# ADS-228.net
KiCad netlist of a schematic drawn in Altium Designer
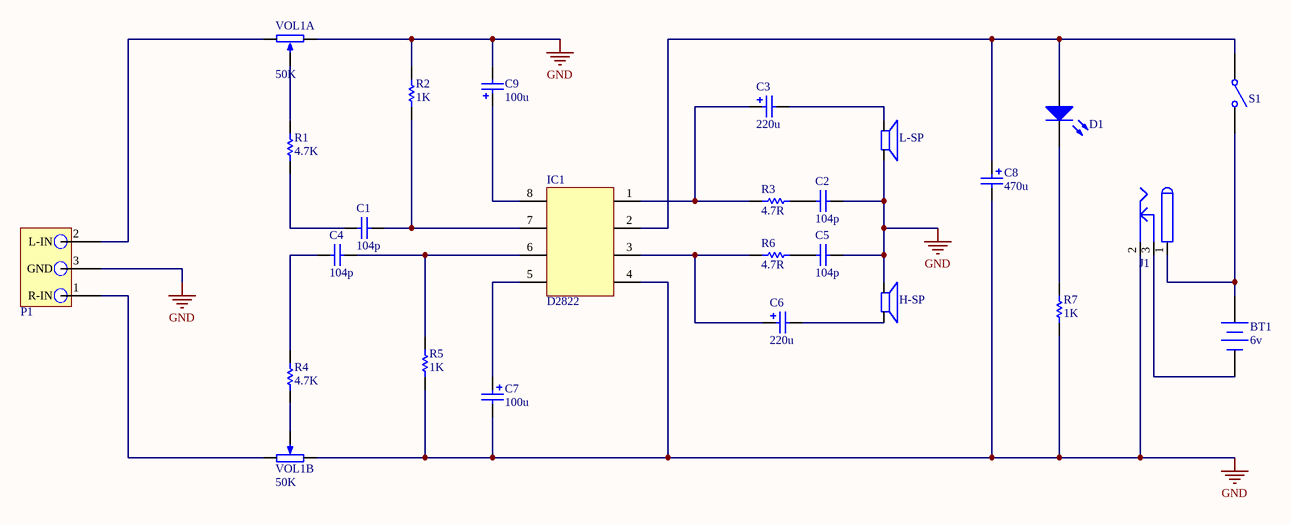
[diagram p0: ADS-228.SchDoc]

(export (version "E")
  (design (tool "Eeschema 10.0.6"))
  (components
    (comp (ref "BT1")
      (value "6v")
      (footprint "BAT")
      (description "Multicell Battery")
      (fields (field (name "PUBLISHER") "Altium Limited"))
      (libsource (lib "ADS-228") (part "Battery"))
    )
    (comp (ref "C1")
      (value "104p")
      (footprint "RAD3")
      (description "Capacitor")
      (fields (field (name "Comment") "Cap") (field (name "PUBLISHER") "Altium Limited"))
      (libsource (lib "ADS-228") (part "Cap"))
    )
    (comp (ref "C2")
      (value "104p")
      (footprint "RAD3")
      (description "Capacitor")
      (fields (field (name "Comment") "Cap") (field (name "PUBLISHER") "Altium Limited"))
      (libsource (lib "ADS-228") (part "Cap"))
    )
    (comp (ref "C3")
      (value "220u")
      (footprint "CAPPR3-5")
      (description "Polarized Capacitor (Radial)")
      (fields (field (name "Comment") "Cap Pol1") (field (name "PUBLISHER") "Altium Limited"))
      (libsource (lib "ADS-228") (part "Cap Pol1"))
    )
    (comp (ref "C4")
      (value "104p")
      (footprint "RAD3")
      (description "Capacitor")
      (fields (field (name "Comment") "Cap") (field (name "PUBLISHER") "Altium Limited"))
      (libsource (lib "ADS-228") (part "Cap"))
    )
    (comp (ref "C5")
      (value "104p")
      (footprint "RAD3")
      (description "Capacitor")
      (fields (field (name "Comment") "Cap") (field (name "PUBLISHER") "Altium Limited"))
      (libsource (lib "ADS-228") (part "Cap"))
    )
    (comp (ref "C6")
      (value "220u")
      (footprint "CAPPR3-5")
      (description "Polarized Capacitor (Radial)")
      (fields (field (name "Comment") "Cap Pol1") (field (name "PUBLISHER") "Altium Limited"))
      (libsource (lib "ADS-228") (part "Cap Pol1"))
    )
    (comp (ref "C7")
      (value "100u")
      (footprint "CAPPR4-6")
      (description "Polarized Capacitor (Radial)")
      (fields (field (name "Comment") "Cap Pol1") (field (name "PUBLISHER") "Altium Limited"))
      (libsource (lib "ADS-228") (part "Cap Pol1"))
    )
    (comp (ref "C8")
      (value "470u")
      (footprint "CAPPR4-6")
      (description "Polarized Capacitor (Radial)")
      (fields (field (name "Comment") "Cap Pol1") (field (name "PUBLISHER") "Altium Limited"))
      (libsource (lib "ADS-228") (part "Cap Pol1"))
    )
    (comp (ref "C9")
      (value "100u")
      (footprint "CAPPR3-5")
      (description "Polarized Capacitor (Radial)")
      (fields (field (name "Comment") "Cap Pol1") (field (name "PUBLISHER") "Altium Limited"))
      (libsource (lib "ADS-228") (part "Cap Pol1"))
    )
    (comp (ref "D1")
      (value "LED1")
      (footprint "LED")
      (description "Typical RED GaAs LED")
      (fields (field (name "PUBLISHER") "Altium Limited"))
      (libsource (lib "ADS-228") (part "LED1"))
    )
    (comp (ref "H-SP") (value "SPEAKER") (footprint "SPAKER2") (libsource (lib "ADS-228") (part "SPEAKER")))
    (comp (ref "IC1") (value "D2822") (footprint "DIP8") (libsource (lib "ADS-228") (part "D2822")))
    (comp (ref "J1")
      (value "PWR2.5")
      (footprint "DC")
      (description "Low Voltage Power Supply Connector")
      (fields (field (name "PUBLISHER") "Altium Limited"))
      (libsource (lib "ADS-228") (part "PWR2.5"))
    )
    (comp (ref "L-SP") (value "SPEAKER") (footprint "SPAKER2") (libsource (lib "ADS-228") (part "SPEAKER")))
    (comp (ref "P1") (value "PLUG") (footprint "HDR1X3") (libsource (lib "ADS-228") (part "PLUG")))
    (comp (ref "R1")
      (value "4.7K")
      (footprint "AXIAL3")
      (description "Resistor")
      (fields (field (name "Comment") "Res1") (field (name "PUBLISHER") "Altium Limited"))
      (libsource (lib "ADS-228") (part "Res1"))
    )
    (comp (ref "R2")
      (value "1K")
      (footprint "AXIAL3")
      (description "Resistor")
      (fields (field (name "Comment") "Res1") (field (name "PUBLISHER") "Altium Limited"))
      (libsource (lib "ADS-228") (part "Res1"))
    )
    (comp (ref "R3")
      (value "4.7R")
      (footprint "AXIAL3")
      (description "Resistor")
      (fields (field (name "Comment") "Res1") (field (name "PUBLISHER") "Altium Limited"))
      (libsource (lib "ADS-228") (part "Res1"))
    )
    (comp (ref "R4")
      (value "4.7K")
      (footprint "AXIAL3")
      (description "Resistor")
      (fields (field (name "Comment") "Res1") (field (name "PUBLISHER") "Altium Limited"))
      (libsource (lib "ADS-228") (part "Res1"))
    )
    (comp (ref "R5")
      (value "1K")
      (footprint "AXIAL3.8")
      (description "Resistor")
      (fields (field (name "Comment") "Res1") (field (name "PUBLISHER") "Altium Limited"))
      (libsource (lib "ADS-228") (part "Res1"))
    )
    (comp (ref "R6")
      (value "4.7R")
      (footprint "AXIAL3")
      (description "Resistor")
      (fields (field (name "Comment") "Res1") (field (name "PUBLISHER") "Altium Limited"))
      (libsource (lib "ADS-228") (part "Res1"))
    )
    (comp (ref "R7")
      (value "1K")
      (footprint "AXIAL5")
      (description "Resistor")
      (fields (field (name "Comment") "Res1") (field (name "PUBLISHER") "Altium Limited"))
      (libsource (lib "ADS-228") (part "Res1"))
    )
    (comp (ref "S1")
      (value "SW-SPST")
      (footprint "SW")
      (description "Single-Pole, Single-Throw Switch")
      (fields (field (name "PUBLISHER") "Altium Limited"))
      (libsource (lib "ADS-228") (part "SW-SPST"))
    )
    (comp (ref "VOL1")
      (value "50K")
      (footprint "VR")
      (fields (field (name "Comment") "RPOT"))
      (libsource (lib "ADS-228") (part "RPOT"))
    )
  )
  (nets
    (net (code "1") (name "GND") (class "Default")
      (node (ref "C2") (pin "2") (pinfunction "2_2") (pintype "passive"))
      (node (ref "C5") (pin "2") (pinfunction "2_2") (pintype "passive"))
      (node (ref "C7") (pin "2") (pinfunction "2_2") (pintype "passive"))
      (node (ref "C8") (pin "2") (pinfunction "2_2") (pintype "passive"))
      (node (ref "C9") (pin "2") (pinfunction "2_2") (pintype "passive"))
      (node (ref "H-SP") (pin "1") (pinfunction "1_1") (pintype "passive"))
      (node (ref "IC1") (pin "4") (pinfunction "4_4") (pintype "passive"))
      (node (ref "J1") (pin "2") (pinfunction "2_2") (pintype "power_in"))
      (node (ref "L-SP") (pin "2") (pinfunction "2_2") (pintype "passive"))
      (node (ref "P1") (pin "3") (pinfunction "GND_3") (pintype "power_in"))
      (node (ref "R2") (pin "2") (pinfunction "2_2") (pintype "passive"))
      (node (ref "R5") (pin "1") (pinfunction "1_1") (pintype "passive"))
      (node (ref "R7") (pin "1") (pinfunction "1_1") (pintype "passive"))
      (node (ref "S1") (pin "0") (pinfunction "GND_0") (pintype "power_in"))
      (node (ref "VOL1") (pin "0") (pinfunction "GND_0") (pintype "power_in"))
      (node (ref "VOL1") (pin "2") (pinfunction "2_2") (pintype "passive"))
    )
    (net (code "2") (name "Net-(BT1-+)") (class "Default")
      (node (ref "BT1") (pin "1") (pinfunction "+_1") (pintype "passive"))
      (node (ref "J1") (pin "1") (pinfunction "1_1") (pintype "power_in"))
      (node (ref "S1") (pin "2") (pinfunction "2_2") (pintype "passive"))
    )
    (net (code "3") (name "Net-(BT1--)") (class "Default")
      (node (ref "BT1") (pin "2") (pinfunction "-_2") (pintype "passive"))
      (node (ref "J1") (pin "3") (pinfunction "3_3") (pintype "power_in"))
    )
    (net (code "4") (name "Net-(C1-Pad1)") (class "Default")
      (node (ref "C1") (pin "1") (pinfunction "1_1") (pintype "passive"))
      (node (ref "R1") (pin "1") (pinfunction "1_1") (pintype "passive"))
    )
    (net (code "5") (name "Net-(C1-Pad2)") (class "Default")
      (node (ref "C1") (pin "2") (pinfunction "2_2") (pintype "passive"))
      (node (ref "IC1") (pin "7") (pinfunction "7_7") (pintype "passive"))
      (node (ref "R2") (pin "1") (pinfunction "1_1") (pintype "passive"))
    )
    (net (code "6") (name "Net-(C2-Pad1)") (class "Default")
      (node (ref "C2") (pin "1") (pinfunction "1_1") (pintype "passive"))
      (node (ref "R3") (pin "2") (pinfunction "2_2") (pintype "passive"))
    )
    (net (code "7") (name "Net-(C3-Pad1)") (class "Default")
      (node (ref "C3") (pin "1") (pinfunction "1_1") (pintype "passive"))
      (node (ref "IC1") (pin "1") (pinfunction "1_1") (pintype "passive"))
      (node (ref "R3") (pin "1") (pinfunction "1_1") (pintype "passive"))
    )
    (net (code "8") (name "Net-(C3-Pad2)") (class "Default")
      (node (ref "C3") (pin "2") (pinfunction "2_2") (pintype "passive"))
      (node (ref "L-SP") (pin "1") (pinfunction "1_1") (pintype "passive"))
    )
    (net (code "9") (name "Net-(C4-Pad1)") (class "Default")
      (node (ref "C4") (pin "1") (pinfunction "1_1") (pintype "passive"))
      (node (ref "R4") (pin "2") (pinfunction "2_2") (pintype "passive"))
    )
    (net (code "10") (name "Net-(C4-Pad2)") (class "Default")
      (node (ref "C4") (pin "2") (pinfunction "2_2") (pintype "passive"))
      (node (ref "IC1") (pin "6") (pinfunction "6_6") (pintype "passive"))
      (node (ref "R5") (pin "2") (pinfunction "2_2") (pintype "passive"))
    )
    (net (code "11") (name "Net-(C5-Pad1)") (class "Default")
      (node (ref "C5") (pin "1") (pinfunction "1_1") (pintype "passive"))
      (node (ref "R6") (pin "2") (pinfunction "2_2") (pintype "passive"))
    )
    (net (code "12") (name "Net-(C6-Pad1)") (class "Default")
      (node (ref "C6") (pin "1") (pinfunction "1_1") (pintype "passive"))
      (node (ref "IC1") (pin "3") (pinfunction "3_3") (pintype "passive"))
      (node (ref "R6") (pin "1") (pinfunction "1_1") (pintype "passive"))
    )
    (net (code "13") (name "Net-(C6-Pad2)") (class "Default")
      (node (ref "C6") (pin "2") (pinfunction "2_2") (pintype "passive"))
      (node (ref "H-SP") (pin "2") (pinfunction "2_2") (pintype "passive"))
    )
    (net (code "14") (name "Net-(C7-Pad1)") (class "Default")
      (node (ref "C7") (pin "1") (pinfunction "1_1") (pintype "passive"))
      (node (ref "IC1") (pin "5") (pinfunction "5_5") (pintype "passive"))
    )
    (net (code "15") (name "Net-(C9-Pad1)") (class "Default")
      (node (ref "C9") (pin "1") (pinfunction "1_1") (pintype "passive"))
      (node (ref "IC1") (pin "8") (pinfunction "8_8") (pintype "passive"))
    )
    (net (code "16") (name "Net-(D1-A)") (class "Default")
      (node (ref "C8") (pin "1") (pinfunction "1_1") (pintype "passive"))
      (node (ref "D1") (pin "1") (pinfunction "A_1") (pintype "passive"))
      (node (ref "IC1") (pin "2") (pinfunction "2_2") (pintype "passive"))
      (node (ref "S1") (pin "1") (pinfunction "1_1") (pintype "passive"))
    )
    (net (code "17") (name "Net-(D1-K)") (class "Default")
      (node (ref "D1") (pin "2") (pinfunction "K_2") (pintype "passive"))
      (node (ref "R7") (pin "2") (pinfunction "2_2") (pintype "passive"))
    )
    (net (code "18") (name "Net-(P1-L-IN)") (class "Default")
      (node (ref "P1") (pin "2") (pinfunction "L-IN_2") (pintype "passive"))
      (node (ref "VOL1") (pin "1") (pinfunction "1_1") (pintype "passive"))
    )
    (net (code "19") (name "Net-(P1-R-IN)") (class "Default")
      (node (ref "P1") (pin "1") (pinfunction "R-IN_1") (pintype "passive"))
      (node (ref "VOL1") (pin "4") (pinfunction "4_4") (pintype "passive"))
    )
    (net (code "20") (name "Net-(R1-Pad2)") (class "Default")
      (node (ref "R1") (pin "2") (pinfunction "2_2") (pintype "passive"))
      (node (ref "VOL1") (pin "3") (pinfunction "3_3") (pintype "passive"))
    )
    (net (code "21") (name "Net-(R4-Pad1)") (class "Default")
      (node (ref "R4") (pin "1") (pinfunction "1_1") (pintype "passive"))
      (node (ref "VOL1") (pin "5") (pinfunction "5_5") (pintype "passive"))
    )
  )
)
